# PCB-2x8GPIO-U.net
KiCad netlist of a schematic drawn in EAGLE
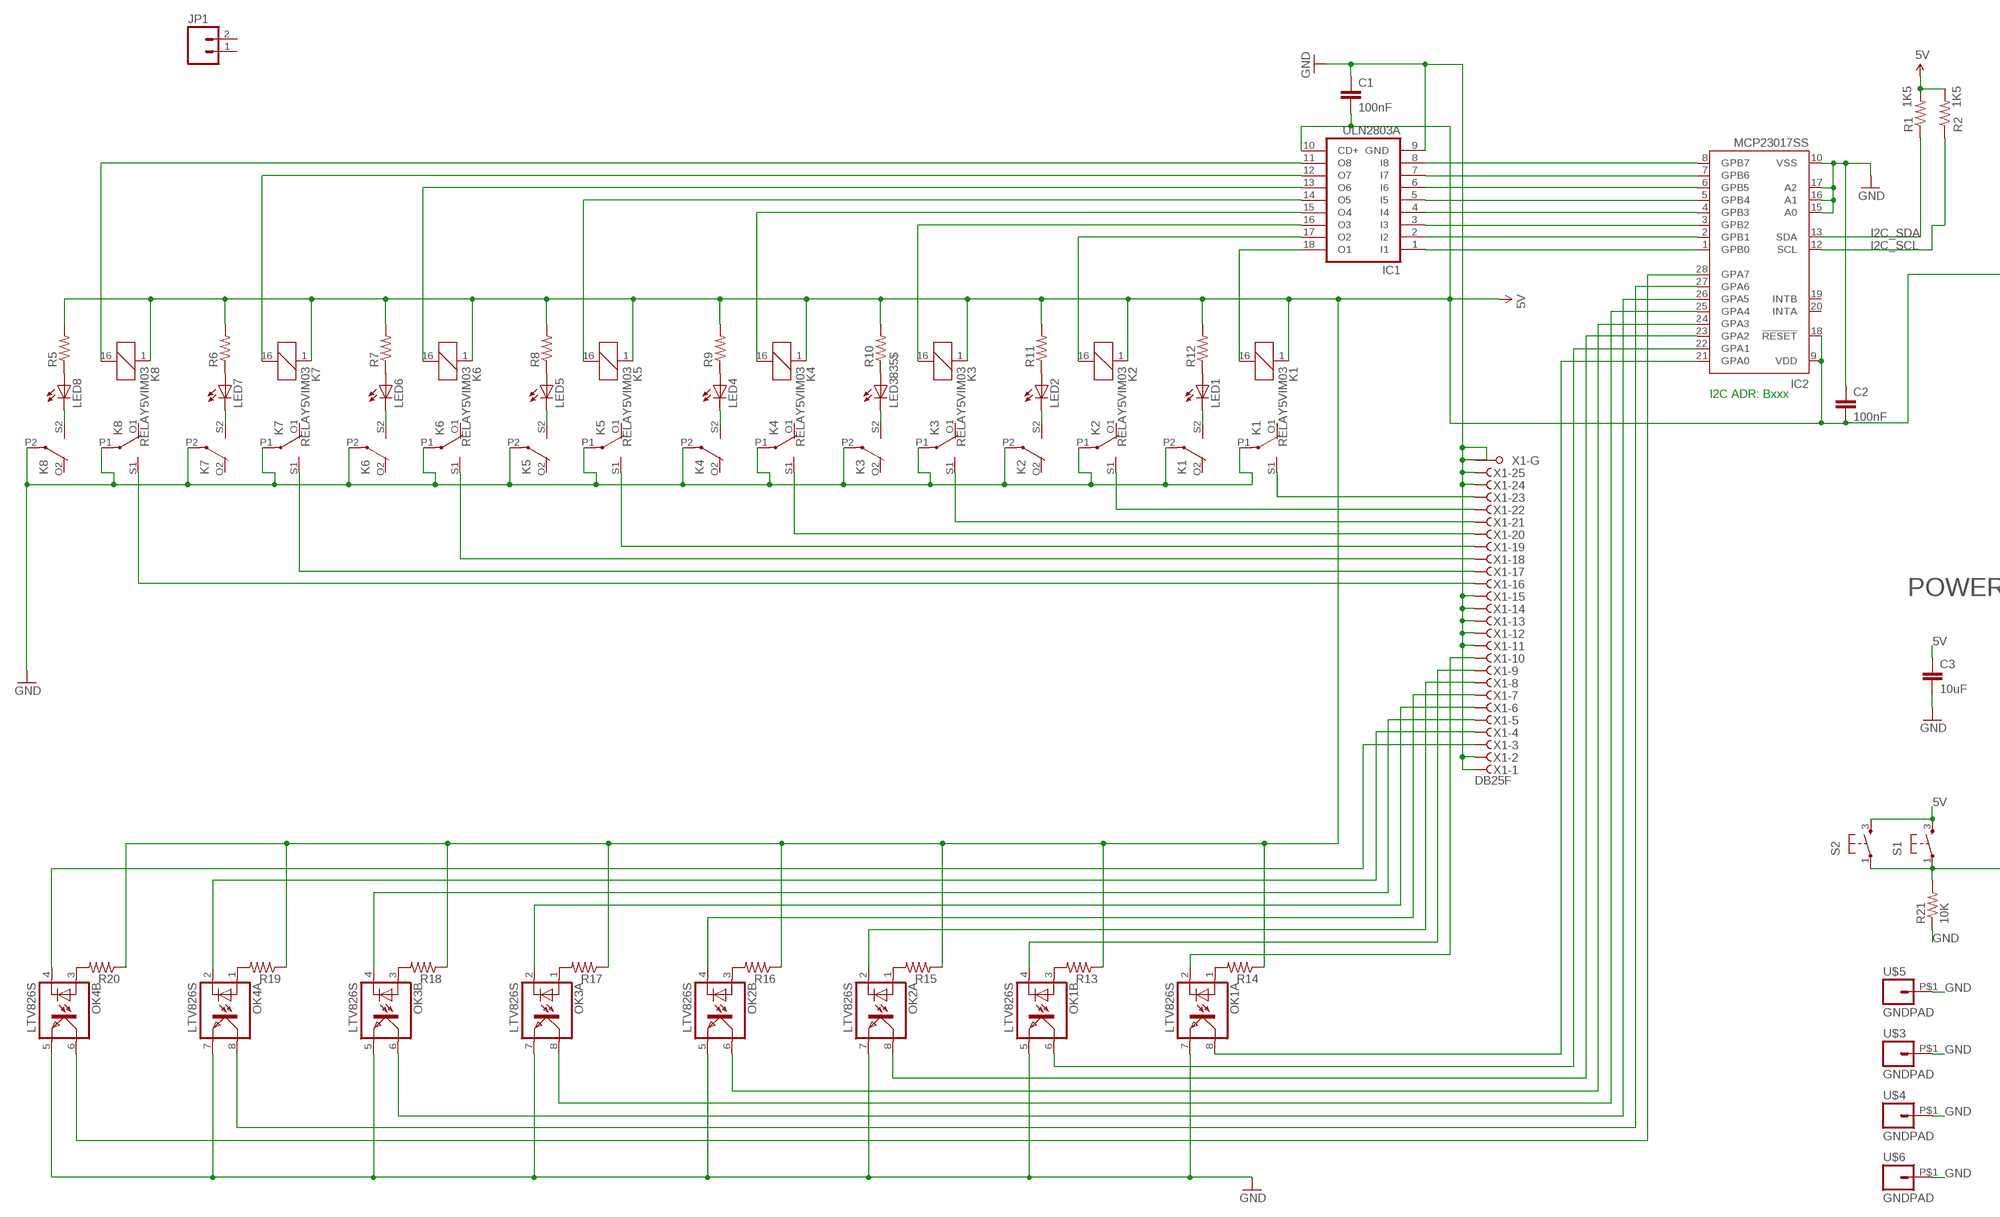
[diagram p0: schematic, sheet 1, part 1 of 2]
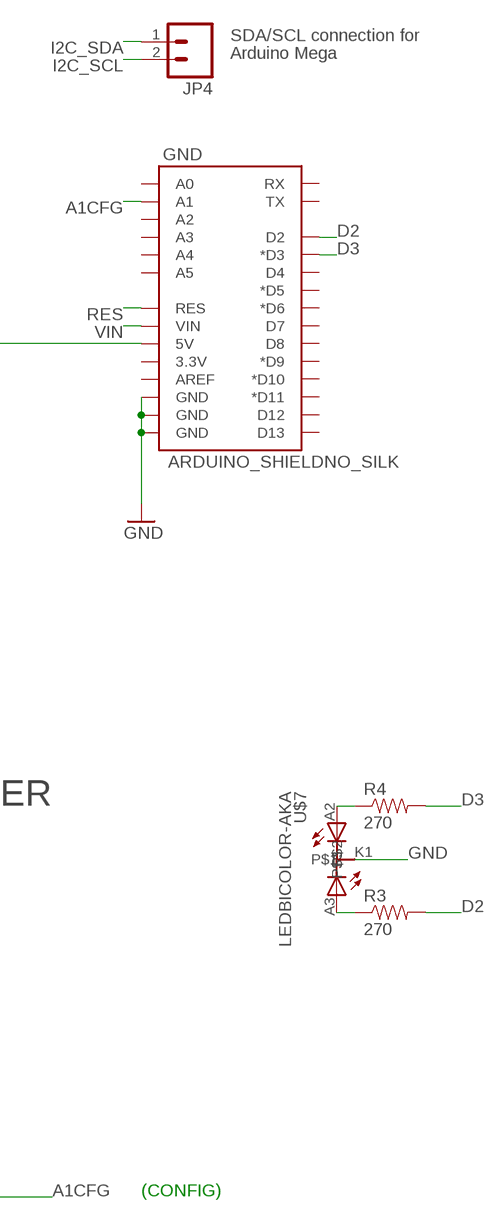
[diagram p1: schematic, sheet 1, part 2 of 2]

(export (version "E")
  (design (tool "Eeschema 10.0.6"))
  (components
    (comp (ref "C1")
      (value "100nF")
      (footprint "eagle-import:0805")
      (libsource (lib "eagle-import") (part "CAP0805"))
    )
    (comp (ref "C2")
      (value "100nF")
      (footprint "eagle-import:0603-CAP")
      (libsource (lib "eagle-import") (part "CAP0603-CAP"))
    )
    (comp (ref "C3")
      (value "10uF")
      (footprint "eagle-import:0805")
      (libsource (lib "eagle-import") (part "CAP0805"))
    )
    (comp (ref "GND")
      (value "ARDUINO_SHIELDNO_SILK")
      (footprint "eagle-import:DUEMILANOVE_VIAS")
      (libsource (lib "eagle-import") (part "ARDUINO_SHIELDNO_SILK"))
    )
    (comp (ref "IC1")
      (value "ULN2803A")
      (footprint "eagle-import:SO18W")
      (libsource (lib "eagle-import") (part "ULN2803ASO18W"))
    )
    (comp (ref "IC2")
      (value "MCP23017SS")
      (footprint "eagle-import:SSOP28")
      (fields (field (name "MF") "MICROCHIP") (field (name "MPN") "MCP23017-E/SS"))
      (libsource (lib "eagle-import") (part "MCP23017SS"))
    )
    (comp (ref "JP1")
      (value "M02PTH")
      (footprint "eagle-import:1X02")
      (libsource (lib "eagle-import") (part "M02PTH"))
    )
    (comp (ref "JP4")
      (value "M02PTH")
      (footprint "eagle-import:1X02")
      (libsource (lib "eagle-import") (part "M02PTH"))
    )
    (comp (ref "K1")
      (value "RELAY5VIM03")
      (footprint "eagle-import:DS2Y")
      (libsource (lib "eagle-import") (part "RELAY5VIM03"))
    )
    (comp (ref "K2")
      (value "RELAY5VIM03")
      (footprint "eagle-import:DS2Y")
      (libsource (lib "eagle-import") (part "RELAY5VIM03"))
    )
    (comp (ref "K3")
      (value "RELAY5VIM03")
      (footprint "eagle-import:DS2Y")
      (libsource (lib "eagle-import") (part "RELAY5VIM03"))
    )
    (comp (ref "K4")
      (value "RELAY5VIM03")
      (footprint "eagle-import:DS2Y")
      (libsource (lib "eagle-import") (part "RELAY5VIM03"))
    )
    (comp (ref "K5")
      (value "RELAY5VIM03")
      (footprint "eagle-import:DS2Y")
      (libsource (lib "eagle-import") (part "RELAY5VIM03"))
    )
    (comp (ref "K6")
      (value "RELAY5VIM03")
      (footprint "eagle-import:DS2Y")
      (libsource (lib "eagle-import") (part "RELAY5VIM03"))
    )
    (comp (ref "K7")
      (value "RELAY5VIM03")
      (footprint "eagle-import:DS2Y")
      (libsource (lib "eagle-import") (part "RELAY5VIM03"))
    )
    (comp (ref "K8")
      (value "RELAY5VIM03")
      (footprint "eagle-import:DS2Y")
      (libsource (lib "eagle-import") (part "RELAY5VIM03"))
    )
    (comp (ref "LED1")
      (value "LED1206")
      (footprint "eagle-import:LED-1206")
      (libsource (lib "eagle-import") (part "LED1206"))
    )
    (comp (ref "LED2")
      (value "LED1206")
      (footprint "eagle-import:LED-1206")
      (libsource (lib "eagle-import") (part "LED1206"))
    )
    (comp (ref "LED4")
      (value "LED1206")
      (footprint "eagle-import:LED-1206")
      (libsource (lib "eagle-import") (part "LED1206"))
    )
    (comp (ref "LED5")
      (value "LED1206")
      (footprint "eagle-import:LED-1206")
      (libsource (lib "eagle-import") (part "LED1206"))
    )
    (comp (ref "LED6")
      (value "LED1206")
      (footprint "eagle-import:LED-1206")
      (libsource (lib "eagle-import") (part "LED1206"))
    )
    (comp (ref "LED7")
      (value "LED1206")
      (footprint "eagle-import:LED-1206")
      (libsource (lib "eagle-import") (part "LED1206"))
    )
    (comp (ref "LED8")
      (value "LED1206")
      (footprint "eagle-import:LED-1206")
      (libsource (lib "eagle-import") (part "LED1206"))
    )
    (comp (ref "LED3835$")
      (value "LED1206")
      (footprint "eagle-import:LED-1206")
      (libsource (lib "eagle-import") (part "LED1206"))
    )
    (comp (ref "OK1")
      (value "LTV826S")
      (footprint "eagle-import:DIL8-SMD")
      (libsource (lib "eagle-import") (part "LTV826S"))
    )
    (comp (ref "OK2")
      (value "LTV826S")
      (footprint "eagle-import:DIL8-SMD")
      (libsource (lib "eagle-import") (part "LTV826S"))
    )
    (comp (ref "OK3")
      (value "LTV826S")
      (footprint "eagle-import:DIL8-SMD")
      (libsource (lib "eagle-import") (part "LTV826S"))
    )
    (comp (ref "OK4")
      (value "LTV826S")
      (footprint "eagle-import:DIL8-SMD")
      (libsource (lib "eagle-import") (part "LTV826S"))
    )
    (comp (ref "R1")
      (value "1K5")
      (footprint "eagle-import:0603-RES")
      (libsource (lib "eagle-import") (part "RESISTOR0603-RES"))
    )
    (comp (ref "R2")
      (value "1K5")
      (footprint "eagle-import:0603-RES")
      (libsource (lib "eagle-import") (part "RESISTOR0603-RES"))
    )
    (comp (ref "R3")
      (value "270")
      (footprint "eagle-import:0603-RES")
      (libsource (lib "eagle-import") (part "RESISTOR0603-RES"))
    )
    (comp (ref "R4")
      (value "270")
      (footprint "eagle-import:0603-RES")
      (libsource (lib "eagle-import") (part "RESISTOR0603-RES"))
    )
    (comp (ref "R5")
      (value "RESISTOR0603-RES")
      (footprint "eagle-import:0603-RES")
      (libsource (lib "eagle-import") (part "RESISTOR0603-RES"))
    )
    (comp (ref "R6")
      (value "RESISTOR0603-RES")
      (footprint "eagle-import:0603-RES")
      (libsource (lib "eagle-import") (part "RESISTOR0603-RES"))
    )
    (comp (ref "R7")
      (value "RESISTOR0603-RES")
      (footprint "eagle-import:0603-RES")
      (libsource (lib "eagle-import") (part "RESISTOR0603-RES"))
    )
    (comp (ref "R8")
      (value "RESISTOR0603-RES")
      (footprint "eagle-import:0603-RES")
      (libsource (lib "eagle-import") (part "RESISTOR0603-RES"))
    )
    (comp (ref "R9")
      (value "RESISTOR0603-RES")
      (footprint "eagle-import:0603-RES")
      (libsource (lib "eagle-import") (part "RESISTOR0603-RES"))
    )
    (comp (ref "R10")
      (value "RESISTOR0603-RES")
      (footprint "eagle-import:0603-RES")
      (libsource (lib "eagle-import") (part "RESISTOR0603-RES"))
    )
    (comp (ref "R11")
      (value "RESISTOR0603-RES")
      (footprint "eagle-import:0603-RES")
      (libsource (lib "eagle-import") (part "RESISTOR0603-RES"))
    )
    (comp (ref "R12")
      (value "RESISTOR0603-RES")
      (footprint "eagle-import:0603-RES")
      (libsource (lib "eagle-import") (part "RESISTOR0603-RES"))
    )
    (comp (ref "R13")
      (value "RESISTOR0603-RES")
      (footprint "eagle-import:0603-RES")
      (libsource (lib "eagle-import") (part "RESISTOR0603-RES"))
    )
    (comp (ref "R14")
      (value "RESISTOR0603-RES")
      (footprint "eagle-import:0603-RES")
      (libsource (lib "eagle-import") (part "RESISTOR0603-RES"))
    )
    (comp (ref "R15")
      (value "RESISTOR0603-RES")
      (footprint "eagle-import:0603-RES")
      (libsource (lib "eagle-import") (part "RESISTOR0603-RES"))
    )
    (comp (ref "R16")
      (value "RESISTOR0603-RES")
      (footprint "eagle-import:0603-RES")
      (libsource (lib "eagle-import") (part "RESISTOR0603-RES"))
    )
    (comp (ref "R17")
      (value "RESISTOR0603-RES")
      (footprint "eagle-import:0603-RES")
      (libsource (lib "eagle-import") (part "RESISTOR0603-RES"))
    )
    (comp (ref "R18")
      (value "RESISTOR0603-RES")
      (footprint "eagle-import:0603-RES")
      (libsource (lib "eagle-import") (part "RESISTOR0603-RES"))
    )
    (comp (ref "R19")
      (value "RESISTOR0603-RES")
      (footprint "eagle-import:0603-RES")
      (libsource (lib "eagle-import") (part "RESISTOR0603-RES"))
    )
    (comp (ref "R20")
      (value "RESISTOR0603-RES")
      (footprint "eagle-import:0603-RES")
      (libsource (lib "eagle-import") (part "RESISTOR0603-RES"))
    )
    (comp (ref "R21")
      (value "10K")
      (footprint "eagle-import:0603-RES")
      (libsource (lib "eagle-import") (part "RESISTOR0603-RES"))
    )
    (comp (ref "S1")
      (value "TAC_SWITCH")
      (footprint "eagle-import:PUSHBUTTON")
      (libsource (lib "eagle-import") (part "TAC_SWITCH"))
    )
    (comp (ref "S2")
      (value "TAC_SWITCH")
      (footprint "eagle-import:PUSHBUTTON")
      (libsource (lib "eagle-import") (part "TAC_SWITCH"))
    )
    (comp (ref "U$3")
      (value "GNDPAD")
      (footprint "eagle-import:3.2MMPAD")
      (libsource (lib "eagle-import") (part "GNDPAD"))
    )
    (comp (ref "U$4")
      (value "GNDPAD")
      (footprint "eagle-import:3.2MMPAD")
      (libsource (lib "eagle-import") (part "GNDPAD"))
    )
    (comp (ref "U$5")
      (value "GNDPAD")
      (footprint "eagle-import:3.2MMPAD")
      (libsource (lib "eagle-import") (part "GNDPAD"))
    )
    (comp (ref "U$6")
      (value "GNDPAD")
      (footprint "eagle-import:3.2MMPAD")
      (libsource (lib "eagle-import") (part "GNDPAD"))
    )
    (comp (ref "U$7")
      (value "LEDBICOLOR-AKA")
      (footprint "eagle-import:LED5MM-BICOLOR")
      (libsource (lib "eagle-import") (part "LEDBICOLOR-AKA"))
    )
    (comp (ref "X1")
      (value "DB25F")
      (footprint "eagle-import:F25HP")
      (libsource (lib "eagle-import") (part "F25HPS"))
    )
  )
  (nets
    (net (code "1") (name "5V") (class "Default")
      (node (ref "C1") (pin "2") (pinfunction "2_2") (pintype "passive"))
      (node (ref "C2") (pin "2") (pinfunction "2_2") (pintype "passive"))
      (node (ref "C3") (pin "1") (pinfunction "1_1") (pintype "passive"))
      (node (ref "GND") (pin "5V") (pinfunction "5V_5V") (pintype "bidirectional"))
      (node (ref "IC1") (pin "10") (pinfunction "CD+_10") (pintype "passive"))
      (node (ref "IC2") (pin "18") (pinfunction "~{RESET}_18") (pintype "input"))
      (node (ref "IC2") (pin "9") (pinfunction "VDD_9") (pintype "power_in"))
      (node (ref "K1") (pin "1") (pinfunction "1_1") (pintype "passive"))
      (node (ref "K2") (pin "1") (pinfunction "1_1") (pintype "passive"))
      (node (ref "K3") (pin "1") (pinfunction "1_1") (pintype "passive"))
      (node (ref "K4") (pin "1") (pinfunction "1_1") (pintype "passive"))
      (node (ref "K5") (pin "1") (pinfunction "1_1") (pintype "passive"))
      (node (ref "K6") (pin "1") (pinfunction "1_1") (pintype "passive"))
      (node (ref "K7") (pin "1") (pinfunction "1_1") (pintype "passive"))
      (node (ref "K8") (pin "1") (pinfunction "1_1") (pintype "passive"))
      (node (ref "R1") (pin "2") (pinfunction "2_2") (pintype "passive"))
      (node (ref "R10") (pin "2") (pinfunction "2_2") (pintype "passive"))
      (node (ref "R11") (pin "2") (pinfunction "2_2") (pintype "passive"))
      (node (ref "R12") (pin "2") (pinfunction "2_2") (pintype "passive"))
      (node (ref "R13") (pin "1") (pinfunction "1_1") (pintype "passive"))
      (node (ref "R14") (pin "1") (pinfunction "1_1") (pintype "passive"))
      (node (ref "R15") (pin "1") (pinfunction "1_1") (pintype "passive"))
      (node (ref "R16") (pin "1") (pinfunction "1_1") (pintype "passive"))
      (node (ref "R17") (pin "1") (pinfunction "1_1") (pintype "passive"))
      (node (ref "R18") (pin "1") (pinfunction "1_1") (pintype "passive"))
      (node (ref "R19") (pin "1") (pinfunction "1_1") (pintype "passive"))
      (node (ref "R2") (pin "2") (pinfunction "2_2") (pintype "passive"))
      (node (ref "R20") (pin "1") (pinfunction "1_1") (pintype "passive"))
      (node (ref "R5") (pin "2") (pinfunction "2_2") (pintype "passive"))
      (node (ref "R6") (pin "2") (pinfunction "2_2") (pintype "passive"))
      (node (ref "R7") (pin "2") (pinfunction "2_2") (pintype "passive"))
      (node (ref "R8") (pin "2") (pinfunction "2_2") (pintype "passive"))
      (node (ref "R9") (pin "2") (pinfunction "2_2") (pintype "passive"))
      (node (ref "S1") (pin "3") (pinfunction "3_3") (pintype "passive"))
      (node (ref "S2") (pin "3") (pinfunction "3_3") (pintype "passive"))
    )
    (net (code "2") (name "A1CFG") (class "Default")
      (node (ref "GND") (pin "A1") (pinfunction "A1_A1") (pintype "bidirectional"))
      (node (ref "R21") (pin "2") (pinfunction "2_2") (pintype "passive"))
      (node (ref "S1") (pin "1") (pinfunction "1_1") (pintype "passive"))
      (node (ref "S2") (pin "1") (pinfunction "1_1") (pintype "passive"))
    )
    (net (code "3") (name "D2") (class "Default")
      (node (ref "GND") (pin "D2") (pinfunction "D2_D2") (pintype "bidirectional"))
      (node (ref "R3") (pin "2") (pinfunction "2_2") (pintype "passive"))
    )
    (net (code "4") (name "D3") (class "Default")
      (node (ref "GND") (pin "D3") (pinfunction "*D3_D3") (pintype "bidirectional"))
      (node (ref "R4") (pin "2") (pinfunction "2_2") (pintype "passive"))
    )
    (net (code "5") (name "GND") (class "Default")
      (node (ref "C1") (pin "1") (pinfunction "1_1") (pintype "passive"))
      (node (ref "C2") (pin "1") (pinfunction "1_1") (pintype "passive"))
      (node (ref "C3") (pin "2") (pinfunction "2_2") (pintype "passive"))
      (node (ref "GND") (pin "GND@0") (pinfunction "GND_GND@0") (pintype "bidirectional"))
      (node (ref "GND") (pin "GND@1") (pinfunction "GND_GND@1") (pintype "bidirectional"))
      (node (ref "GND") (pin "GND@2") (pinfunction "GND_GND@2") (pintype "bidirectional"))
      (node (ref "IC1") (pin "9") (pinfunction "GND_9") (pintype "power_in"))
      (node (ref "IC2") (pin "10") (pinfunction "VSS_10") (pintype "power_in"))
      (node (ref "IC2") (pin "15") (pinfunction "A0_15") (pintype "input"))
      (node (ref "IC2") (pin "16") (pinfunction "A1_16") (pintype "input"))
      (node (ref "IC2") (pin "17") (pinfunction "A2_17") (pintype "input"))
      (node (ref "K1") (pin "P1") (pinfunction "P_P1") (pintype "passive"))
      (node (ref "K1") (pin "P2") (pinfunction "P_P2") (pintype "passive"))
      (node (ref "K2") (pin "P1") (pinfunction "P_P1") (pintype "passive"))
      (node (ref "K2") (pin "P2") (pinfunction "P_P2") (pintype "passive"))
      (node (ref "K3") (pin "P1") (pinfunction "P_P1") (pintype "passive"))
      (node (ref "K3") (pin "P2") (pinfunction "P_P2") (pintype "passive"))
      (node (ref "K4") (pin "P1") (pinfunction "P_P1") (pintype "passive"))
      (node (ref "K4") (pin "P2") (pinfunction "P_P2") (pintype "passive"))
      (node (ref "K5") (pin "P1") (pinfunction "P_P1") (pintype "passive"))
      (node (ref "K5") (pin "P2") (pinfunction "P_P2") (pintype "passive"))
      (node (ref "K6") (pin "P1") (pinfunction "P_P1") (pintype "passive"))
      (node (ref "K6") (pin "P2") (pinfunction "P_P2") (pintype "passive"))
      (node (ref "K7") (pin "P1") (pinfunction "P_P1") (pintype "passive"))
      (node (ref "K7") (pin "P2") (pinfunction "P_P2") (pintype "passive"))
      (node (ref "K8") (pin "P1") (pinfunction "P_P1") (pintype "passive"))
      (node (ref "K8") (pin "P2") (pinfunction "P_P2") (pintype "passive"))
      (node (ref "OK1") (pin "5") (pinfunction "EMIT_5") (pintype "passive"))
      (node (ref "OK1") (pin "7") (pinfunction "EMIT_7") (pintype "passive"))
      (node (ref "OK2") (pin "5") (pinfunction "EMIT_5") (pintype "passive"))
      (node (ref "OK2") (pin "7") (pinfunction "EMIT_7") (pintype "passive"))
      (node (ref "OK3") (pin "5") (pinfunction "EMIT_5") (pintype "passive"))
      (node (ref "OK3") (pin "7") (pinfunction "EMIT_7") (pintype "passive"))
      (node (ref "OK4") (pin "5") (pinfunction "EMIT_5") (pintype "passive"))
      (node (ref "OK4") (pin "7") (pinfunction "EMIT_7") (pintype "passive"))
      (node (ref "R21") (pin "1") (pinfunction "1_1") (pintype "passive"))
      (node (ref "U$3") (pin "P$1") (pinfunction "1_P$1") (pintype "passive"))
      (node (ref "U$4") (pin "P$1") (pinfunction "1_P$1") (pintype "passive"))
      (node (ref "U$5") (pin "P$1") (pinfunction "1_P$1") (pintype "passive"))
      (node (ref "U$6") (pin "P$1") (pinfunction "1_P$1") (pintype "passive"))
      (node (ref "U$7") (pin "K1") (pinfunction "P$1_K1") (pintype "bidirectional"))
      (node (ref "X1") (pin "1") (pinfunction "F_1") (pintype "passive"))
      (node (ref "X1") (pin "11") (pinfunction "F_11") (pintype "passive"))
      (node (ref "X1") (pin "12") (pinfunction "F_12") (pintype "passive"))
      (node (ref "X1") (pin "13") (pinfunction "F_13") (pintype "passive"))
      (node (ref "X1") (pin "14") (pinfunction "F_14") (pintype "passive"))
      (node (ref "X1") (pin "15") (pinfunction "F_15") (pintype "passive"))
      (node (ref "X1") (pin "2") (pinfunction "F_2") (pintype "passive"))
      (node (ref "X1") (pin "24") (pinfunction "F_24") (pintype "passive"))
      (node (ref "X1") (pin "25") (pinfunction "F_25") (pintype "passive"))
      (node (ref "X1") (pin "G1") (pinfunction "G1_G1") (pintype "passive"))
      (node (ref "X1") (pin "G2") (pinfunction "G2_G2") (pintype "passive"))
    )
    (net (code "6") (name "I2C_SCL") (class "Default")
      (node (ref "IC2") (pin "12") (pinfunction "SCL_12") (pintype "input"))
      (node (ref "JP4") (pin "2") (pinfunction "2_2") (pintype "passive"))
      (node (ref "R2") (pin "1") (pinfunction "1_1") (pintype "passive"))
    )
    (net (code "7") (name "I2C_SDA") (class "Default")
      (node (ref "IC2") (pin "13") (pinfunction "SDA_13") (pintype "bidirectional"))
      (node (ref "JP4") (pin "1") (pinfunction "1_1") (pintype "passive"))
      (node (ref "R1") (pin "1") (pinfunction "1_1") (pintype "passive"))
    )
    (net (code "8") (name "Net-(IC1-I1)") (class "Default")
      (node (ref "IC1") (pin "1") (pinfunction "I1_1") (pintype "input"))
      (node (ref "IC2") (pin "1") (pinfunction "GPB0_1") (pintype "bidirectional"))
    )
    (net (code "9") (name "Net-(IC1-I2)") (class "Default")
      (node (ref "IC1") (pin "2") (pinfunction "I2_2") (pintype "input"))
      (node (ref "IC2") (pin "2") (pinfunction "GPB1_2") (pintype "bidirectional"))
    )
    (net (code "10") (name "Net-(IC1-I3)") (class "Default")
      (node (ref "IC1") (pin "3") (pinfunction "I3_3") (pintype "input"))
      (node (ref "IC2") (pin "3") (pinfunction "GPB2_3") (pintype "bidirectional"))
    )
    (net (code "11") (name "Net-(IC1-I4)") (class "Default")
      (node (ref "IC1") (pin "4") (pinfunction "I4_4") (pintype "input"))
      (node (ref "IC2") (pin "4") (pinfunction "GPB3_4") (pintype "bidirectional"))
    )
    (net (code "12") (name "Net-(IC1-I5)") (class "Default")
      (node (ref "IC1") (pin "5") (pinfunction "I5_5") (pintype "input"))
      (node (ref "IC2") (pin "5") (pinfunction "GPB4_5") (pintype "bidirectional"))
    )
    (net (code "13") (name "Net-(IC1-I6)") (class "Default")
      (node (ref "IC1") (pin "6") (pinfunction "I6_6") (pintype "input"))
      (node (ref "IC2") (pin "6") (pinfunction "GPB5_6") (pintype "bidirectional"))
    )
    (net (code "14") (name "Net-(IC1-I7)") (class "Default")
      (node (ref "IC1") (pin "7") (pinfunction "I7_7") (pintype "input"))
      (node (ref "IC2") (pin "7") (pinfunction "GPB6_7") (pintype "bidirectional"))
    )
    (net (code "15") (name "Net-(IC1-I8)") (class "Default")
      (node (ref "IC1") (pin "8") (pinfunction "I8_8") (pintype "input"))
      (node (ref "IC2") (pin "8") (pinfunction "GPB7_8") (pintype "bidirectional"))
    )
    (net (code "16") (name "Net-(IC1-O1)") (class "Default")
      (node (ref "IC1") (pin "18") (pinfunction "O1_18") (pintype "open_collector"))
      (node (ref "K1") (pin "16") (pinfunction "2_16") (pintype "passive"))
    )
    (net (code "17") (name "Net-(IC1-O2)") (class "Default")
      (node (ref "IC1") (pin "17") (pinfunction "O2_17") (pintype "open_collector"))
      (node (ref "K2") (pin "16") (pinfunction "2_16") (pintype "passive"))
    )
    (net (code "18") (name "Net-(IC1-O3)") (class "Default")
      (node (ref "IC1") (pin "16") (pinfunction "O3_16") (pintype "open_collector"))
      (node (ref "K3") (pin "16") (pinfunction "2_16") (pintype "passive"))
    )
    (net (code "19") (name "Net-(IC1-O4)") (class "Default")
      (node (ref "IC1") (pin "15") (pinfunction "O4_15") (pintype "open_collector"))
      (node (ref "K4") (pin "16") (pinfunction "2_16") (pintype "passive"))
    )
    (net (code "20") (name "Net-(IC1-O5)") (class "Default")
      (node (ref "IC1") (pin "14") (pinfunction "O5_14") (pintype "open_collector"))
      (node (ref "K5") (pin "16") (pinfunction "2_16") (pintype "passive"))
    )
    (net (code "21") (name "Net-(IC1-O6)") (class "Default")
      (node (ref "IC1") (pin "13") (pinfunction "O6_13") (pintype "open_collector"))
      (node (ref "K6") (pin "16") (pinfunction "2_16") (pintype "passive"))
    )
    (net (code "22") (name "Net-(IC1-O7)") (class "Default")
      (node (ref "IC1") (pin "12") (pinfunction "O7_12") (pintype "open_collector"))
      (node (ref "K7") (pin "16") (pinfunction "2_16") (pintype "passive"))
    )
    (net (code "23") (name "Net-(IC1-O8)") (class "Default")
      (node (ref "IC1") (pin "11") (pinfunction "O8_11") (pintype "open_collector"))
      (node (ref "K8") (pin "16") (pinfunction "2_16") (pintype "passive"))
    )
    (net (code "24") (name "Net-(IC2-GPA0)") (class "Default")
      (node (ref "IC2") (pin "21") (pinfunction "GPA0_21") (pintype "bidirectional"))
      (node (ref "OK1") (pin "8") (pinfunction "COL_8") (pintype "passive"))
    )
    (net (code "25") (name "Net-(IC2-GPA1)") (class "Default")
      (node (ref "IC2") (pin "22") (pinfunction "GPA1_22") (pintype "bidirectional"))
      (node (ref "OK1") (pin "6") (pinfunction "COL_6") (pintype "passive"))
    )
    (net (code "26") (name "Net-(IC2-GPA2)") (class "Default")
      (node (ref "IC2") (pin "23") (pinfunction "GPA2_23") (pintype "bidirectional"))
      (node (ref "OK2") (pin "8") (pinfunction "COL_8") (pintype "passive"))
    )
    (net (code "27") (name "Net-(IC2-GPA3)") (class "Default")
      (node (ref "IC2") (pin "24") (pinfunction "GPA3_24") (pintype "bidirectional"))
      (node (ref "OK2") (pin "6") (pinfunction "COL_6") (pintype "passive"))
    )
    (net (code "28") (name "Net-(IC2-GPA4)") (class "Default")
      (node (ref "IC2") (pin "25") (pinfunction "GPA4_25") (pintype "bidirectional"))
      (node (ref "OK3") (pin "8") (pinfunction "COL_8") (pintype "passive"))
    )
    (net (code "29") (name "Net-(IC2-GPA5)") (class "Default")
      (node (ref "IC2") (pin "26") (pinfunction "GPA5_26") (pintype "bidirectional"))
      (node (ref "OK3") (pin "6") (pinfunction "COL_6") (pintype "passive"))
    )
    (net (code "30") (name "Net-(IC2-GPA6)") (class "Default")
      (node (ref "IC2") (pin "27") (pinfunction "GPA6_27") (pintype "bidirectional"))
      (node (ref "OK4") (pin "8") (pinfunction "COL_8") (pintype "passive"))
    )
    (net (code "31") (name "Net-(IC2-GPA7)") (class "Default")
      (node (ref "IC2") (pin "28") (pinfunction "GPA7_28") (pintype "bidirectional"))
      (node (ref "OK4") (pin "6") (pinfunction "COL_6") (pintype "passive"))
    )
    (net (code "32") (name "Net-(K1B-S)") (class "Default")
      (node (ref "K1") (pin "S1") (pinfunction "S_S1") (pintype "passive"))
      (node (ref "X1") (pin "23") (pinfunction "F_23") (pintype "passive"))
    )
    (net (code "33") (name "Net-(K1C-S)") (class "Default")
      (node (ref "K1") (pin "S2") (pinfunction "S_S2") (pintype "passive"))
      (node (ref "LED1") (pin "C") (pinfunction "C_C") (pintype "passive"))
    )
    (net (code "34") (name "Net-(K2B-S)") (class "Default")
      (node (ref "K2") (pin "S1") (pinfunction "S_S1") (pintype "passive"))
      (node (ref "X1") (pin "22") (pinfunction "F_22") (pintype "passive"))
    )
    (net (code "35") (name "Net-(K2C-S)") (class "Default")
      (node (ref "K2") (pin "S2") (pinfunction "S_S2") (pintype "passive"))
      (node (ref "LED2") (pin "C") (pinfunction "C_C") (pintype "passive"))
    )
    (net (code "36") (name "Net-(K3B-S)") (class "Default")
      (node (ref "K3") (pin "S1") (pinfunction "S_S1") (pintype "passive"))
      (node (ref "X1") (pin "21") (pinfunction "F_21") (pintype "passive"))
    )
    (net (code "37") (name "Net-(K3C-S)") (class "Default")
      (node (ref "K3") (pin "S2") (pinfunction "S_S2") (pintype "passive"))
      (node (ref "LED3835$") (pin "C") (pinfunction "C_C") (pintype "passive"))
    )
    (net (code "38") (name "Net-(K4B-S)") (class "Default")
      (node (ref "K4") (pin "S1") (pinfunction "S_S1") (pintype "passive"))
      (node (ref "X1") (pin "20") (pinfunction "F_20") (pintype "passive"))
    )
    (net (code "39") (name "Net-(K4C-S)") (class "Default")
      (node (ref "K4") (pin "S2") (pinfunction "S_S2") (pintype "passive"))
      (node (ref "LED4") (pin "C") (pinfunction "C_C") (pintype "passive"))
    )
    (net (code "40") (name "Net-(K5B-S)") (class "Default")
      (node (ref "K5") (pin "S1") (pinfunction "S_S1") (pintype "passive"))
      (node (ref "X1") (pin "19") (pinfunction "F_19") (pintype "passive"))
    )
    (net (code "41") (name "Net-(K5C-S)") (class "Default")
      (node (ref "K5") (pin "S2") (pinfunction "S_S2") (pintype "passive"))
      (node (ref "LED5") (pin "C") (pinfunction "C_C") (pintype "passive"))
    )
    (net (code "42") (name "Net-(K6B-S)") (class "Default")
      (node (ref "K6") (pin "S1") (pinfunction "S_S1") (pintype "passive"))
      (node (ref "X1") (pin "18") (pinfunction "F_18") (pintype "passive"))
    )
    (net (code "43") (name "Net-(K6C-S)") (class "Default")
      (node (ref "K6") (pin "S2") (pinfunction "S_S2") (pintype "passive"))
      (node (ref "LED6") (pin "C") (pinfunction "C_C") (pintype "passive"))
    )
    (net (code "44") (name "Net-(K7B-S)") (class "Default")
      (node (ref "K7") (pin "S1") (pinfunction "S_S1") (pintype "passive"))
      (node (ref "X1") (pin "17") (pinfunction "F_17") (pintype "passive"))
    )
    (net (code "45") (name "Net-(K7C-S)") (class "Default")
      (node (ref "K7") (pin "S2") (pinfunction "S_S2") (pintype "passive"))
      (node (ref "LED7") (pin "C") (pinfunction "C_C") (pintype "passive"))
    )
    (net (code "46") (name "Net-(K8B-S)") (class "Default")
      (node (ref "K8") (pin "S1") (pinfunction "S_S1") (pintype "passive"))
      (node (ref "X1") (pin "16") (pinfunction "F_16") (pintype "passive"))
    )
    (net (code "47") (name "Net-(K8C-S)") (class "Default")
      (node (ref "K8") (pin "S2") (pinfunction "S_S2") (pintype "passive"))
      (node (ref "LED8") (pin "C") (pinfunction "C_C") (pintype "passive"))
    )
    (net (code "48") (name "Net-(LED1-PadA)") (class "Default")
      (node (ref "LED1") (pin "A") (pinfunction "A_A") (pintype "passive"))
      (node (ref "R12") (pin "1") (pinfunction "1_1") (pintype "passive"))
    )
    (net (code "49") (name "Net-(LED2-PadA)") (class "Default")
      (node (ref "LED2") (pin "A") (pinfunction "A_A") (pintype "passive"))
      (node (ref "R11") (pin "1") (pinfunction "1_1") (pintype "passive"))
    )
    (net (code "50") (name "Net-(LED4-PadA)") (class "Default")
      (node (ref "LED4") (pin "A") (pinfunction "A_A") (pintype "passive"))
      (node (ref "R9") (pin "1") (pinfunction "1_1") (pintype "passive"))
    )
    (net (code "51") (name "Net-(LED5-PadA)") (class "Default")
      (node (ref "LED5") (pin "A") (pinfunction "A_A") (pintype "passive"))
      (node (ref "R8") (pin "1") (pinfunction "1_1") (pintype "passive"))
    )
    (net (code "52") (name "Net-(LED6-PadA)") (class "Default")
      (node (ref "LED6") (pin "A") (pinfunction "A_A") (pintype "passive"))
      (node (ref "R7") (pin "1") (pinfunction "1_1") (pintype "passive"))
    )
    (net (code "53") (name "Net-(LED7-PadA)") (class "Default")
      (node (ref "LED7") (pin "A") (pinfunction "A_A") (pintype "passive"))
      (node (ref "R6") (pin "1") (pinfunction "1_1") (pintype "passive"))
    )
    (net (code "54") (name "Net-(LED8-PadA)") (class "Default")
      (node (ref "LED8") (pin "A") (pinfunction "A_A") (pintype "passive"))
      (node (ref "R5") (pin "1") (pinfunction "1_1") (pintype "passive"))
    )
    (net (code "55") (name "Net-(LED3835$-PadA)") (class "Default")
      (node (ref "LED3835$") (pin "A") (pinfunction "A_A") (pintype "passive"))
      (node (ref "R10") (pin "1") (pinfunction "1_1") (pintype "passive"))
    )
    (net (code "56") (name "Net-(OK1A-A)") (class "Default")
      (node (ref "OK1") (pin "1") (pinfunction "A_1") (pintype "passive"))
      (node (ref "R14") (pin "2") (pinfunction "2_2") (pintype "passive"))
    )
    (net (code "57") (name "Net-(OK1A-C)") (class "Default")
      (node (ref "OK1") (pin "2") (pinfunction "C_2") (pintype "passive"))
      (node (ref "X1") (pin "10") (pinfunction "F_10") (pintype "passive"))
    )
    (net (code "58") (name "Net-(OK1B-A)") (class "Default")
      (node (ref "OK1") (pin "3") (pinfunction "A_3") (pintype "passive"))
      (node (ref "R13") (pin "2") (pinfunction "2_2") (pintype "passive"))
    )
    (net (code "59") (name "Net-(OK1B-C)") (class "Default")
      (node (ref "OK1") (pin "4") (pinfunction "C_4") (pintype "passive"))
      (node (ref "X1") (pin "9") (pinfunction "F_9") (pintype "passive"))
    )
    (net (code "60") (name "Net-(OK2A-A)") (class "Default")
      (node (ref "OK2") (pin "1") (pinfunction "A_1") (pintype "passive"))
      (node (ref "R15") (pin "2") (pinfunction "2_2") (pintype "passive"))
    )
    (net (code "61") (name "Net-(OK2A-C)") (class "Default")
      (node (ref "OK2") (pin "2") (pinfunction "C_2") (pintype "passive"))
      (node (ref "X1") (pin "8") (pinfunction "F_8") (pintype "passive"))
    )
    (net (code "62") (name "Net-(OK2B-A)") (class "Default")
      (node (ref "OK2") (pin "3") (pinfunction "A_3") (pintype "passive"))
      (node (ref "R16") (pin "2") (pinfunction "2_2") (pintype "passive"))
    )
    (net (code "63") (name "Net-(OK2B-C)") (class "Default")
      (node (ref "OK2") (pin "4") (pinfunction "C_4") (pintype "passive"))
      (node (ref "X1") (pin "7") (pinfunction "F_7") (pintype "passive"))
    )
    (net (code "64") (name "Net-(OK3A-A)") (class "Default")
      (node (ref "OK3") (pin "1") (pinfunction "A_1") (pintype "passive"))
      (node (ref "R17") (pin "2") (pinfunction "2_2") (pintype "passive"))
    )
    (net (code "65") (name "Net-(OK3A-C)") (class "Default")
      (node (ref "OK3") (pin "2") (pinfunction "C_2") (pintype "passive"))
      (node (ref "X1") (pin "6") (pinfunction "F_6") (pintype "passive"))
    )
    (net (code "66") (name "Net-(OK3B-A)") (class "Default")
      (node (ref "OK3") (pin "3") (pinfunction "A_3") (pintype "passive"))
      (node (ref "R18") (pin "2") (pinfunction "2_2") (pintype "passive"))
    )
    (net (code "67") (name "Net-(OK3B-C)") (class "Default")
      (node (ref "OK3") (pin "4") (pinfunction "C_4") (pintype "passive"))
      (node (ref "X1") (pin "5") (pinfunction "F_5") (pintype "passive"))
    )
    (net (code "68") (name "Net-(OK4A-A)") (class "Default")
      (node (ref "OK4") (pin "1") (pinfunction "A_1") (pintype "passive"))
      (node (ref "R19") (pin "2") (pinfunction "2_2") (pintype "passive"))
    )
    (net (code "69") (name "Net-(OK4A-C)") (class "Default")
      (node (ref "OK4") (pin "2") (pinfunction "C_2") (pintype "passive"))
      (node (ref "X1") (pin "4") (pinfunction "F_4") (pintype "passive"))
    )
    (net (code "70") (name "Net-(OK4B-A)") (class "Default")
      (node (ref "OK4") (pin "3") (pinfunction "A_3") (pintype "passive"))
      (node (ref "R20") (pin "2") (pinfunction "2_2") (pintype "passive"))
    )
    (net (code "71") (name "Net-(OK4B-C)") (class "Default")
      (node (ref "OK4") (pin "4") (pinfunction "C_4") (pintype "passive"))
      (node (ref "X1") (pin "3") (pinfunction "F_3") (pintype "passive"))
    )
    (net (code "72") (name "Net-(U$7-P$2)") (class "Default")
      (node (ref "R4") (pin "1") (pinfunction "1_1") (pintype "passive"))
      (node (ref "U$7") (pin "A2") (pinfunction "P$2_A2") (pintype "bidirectional"))
    )
    (net (code "73") (name "Net-(U$7-P$3)") (class "Default")
      (node (ref "R3") (pin "1") (pinfunction "1_1") (pintype "passive"))
      (node (ref "U$7") (pin "A3") (pinfunction "P$3_A3") (pintype "bidirectional"))
    )
    (net (code "74") (name "RES") (class "Default")
      (node (ref "GND") (pin "RES") (pinfunction "RES_RES") (pintype "bidirectional"))
    )
    (net (code "75") (name "VIN") (class "Default")
      (node (ref "GND") (pin "VIN") (pinfunction "VIN_VIN") (pintype "bidirectional"))
    )
    (net (code "76") (name "unconnected-(GND-*D5-PadD5)") (class "Default")
      (node (ref "GND") (pin "D5") (pinfunction "*D5_D5") (pintype "bidirectional"))
    )
    (net (code "77") (name "unconnected-(GND-*D6-PadD6)") (class "Default")
      (node (ref "GND") (pin "D6") (pinfunction "*D6_D6") (pintype "bidirectional"))
    )
    (net (code "78") (name "unconnected-(GND-*D9-PadD9)") (class "Default")
      (node (ref "GND") (pin "D9") (pinfunction "*D9_D9") (pintype "bidirectional"))
    )
    (net (code "79") (name "unconnected-(GND-*D10-PadD10)") (class "Default")
      (node (ref "GND") (pin "D10") (pinfunction "*D10_D10") (pintype "bidirectional"))
    )
    (net (code "80") (name "unconnected-(GND-*D11-PadD11)") (class "Default")
      (node (ref "GND") (pin "D11") (pinfunction "*D11_D11") (pintype "bidirectional"))
    )
    (net (code "81") (name "unconnected-(GND-Pad3.3V)") (class "Default")
      (node (ref "GND") (pin "3.3V") (pinfunction "3.3V_3.3V") (pintype "bidirectional"))
    )
    (net (code "82") (name "unconnected-(GND-PadA0)") (class "Default")
      (node (ref "GND") (pin "A0") (pinfunction "A0_A0") (pintype "bidirectional"))
    )
    (net (code "83") (name "unconnected-(GND-PadA2)") (class "Default")
      (node (ref "GND") (pin "A2") (pinfunction "A2_A2") (pintype "bidirectional"))
    )
    (net (code "84") (name "unconnected-(GND-PadA3)") (class "Default")
      (node (ref "GND") (pin "A3") (pinfunction "A3_A3") (pintype "bidirectional"))
    )
    (net (code "85") (name "unconnected-(GND-PadA4)") (class "Default")
      (node (ref "GND") (pin "A4") (pinfunction "A4_A4") (pintype "bidirectional"))
    )
    (net (code "86") (name "unconnected-(GND-PadA5)") (class "Default")
      (node (ref "GND") (pin "A5") (pinfunction "A5_A5") (pintype "bidirectional"))
    )
    (net (code "87") (name "unconnected-(GND-PadAREF)") (class "Default")
      (node (ref "GND") (pin "AREF") (pinfunction "AREF_AREF") (pintype "bidirectional"))
    )
    (net (code "88") (name "unconnected-(GND-PadD4)") (class "Default")
      (node (ref "GND") (pin "D4") (pinfunction "D4_D4") (pintype "bidirectional"))
    )
    (net (code "89") (name "unconnected-(GND-PadD7)") (class "Default")
      (node (ref "GND") (pin "D7") (pinfunction "D7_D7") (pintype "bidirectional"))
    )
    (net (code "90") (name "unconnected-(GND-PadD8)") (class "Default")
      (node (ref "GND") (pin "D8") (pinfunction "D8_D8") (pintype "bidirectional"))
    )
    (net (code "91") (name "unconnected-(GND-PadD12)") (class "Default")
      (node (ref "GND") (pin "D12") (pinfunction "D12_D12") (pintype "bidirectional"))
    )
    (net (code "92") (name "unconnected-(GND-PadD13)") (class "Default")
      (node (ref "GND") (pin "D13") (pinfunction "D13_D13") (pintype "bidirectional"))
    )
    (net (code "93") (name "unconnected-(GND-PadRX)") (class "Default")
      (node (ref "GND") (pin "RX") (pinfunction "RX_RX") (pintype "bidirectional"))
    )
    (net (code "94") (name "unconnected-(GND-PadTX)") (class "Default")
      (node (ref "GND") (pin "TX") (pinfunction "TX_TX") (pintype "bidirectional"))
    )
    (net (code "95") (name "unconnected-(IC2-INTA-Pad20)") (class "Default")
      (node (ref "IC2") (pin "20") (pinfunction "INTA_20") (pintype "output"))
    )
    (net (code "96") (name "unconnected-(IC2-INTB-Pad19)") (class "Default")
      (node (ref "IC2") (pin "19") (pinfunction "INTB_19") (pintype "output"))
    )
    (net (code "97") (name "unconnected-(JP1-Pad1)") (class "Default")
      (node (ref "JP1") (pin "1") (pinfunction "1_1") (pintype "passive"))
    )
    (net (code "98") (name "unconnected-(JP1-Pad2)") (class "Default")
      (node (ref "JP1") (pin "2") (pinfunction "2_2") (pintype "passive"))
    )
    (net (code "99") (name "unconnected-(K1B-O-PadO1)") (class "Default")
      (node (ref "K1") (pin "O1") (pinfunction "O_O1") (pintype "passive"))
    )
    (net (code "100") (name "unconnected-(K1C-O-PadO2)") (class "Default")
      (node (ref "K1") (pin "O2") (pinfunction "O_O2") (pintype "passive"))
    )
    (net (code "101") (name "unconnected-(K2B-O-PadO1)") (class "Default")
      (node (ref "K2") (pin "O1") (pinfunction "O_O1") (pintype "passive"))
    )
    (net (code "102") (name "unconnected-(K2C-O-PadO2)") (class "Default")
      (node (ref "K2") (pin "O2") (pinfunction "O_O2") (pintype "passive"))
    )
    (net (code "103") (name "unconnected-(K3B-O-PadO1)") (class "Default")
      (node (ref "K3") (pin "O1") (pinfunction "O_O1") (pintype "passive"))
    )
    (net (code "104") (name "unconnected-(K3C-O-PadO2)") (class "Default")
      (node (ref "K3") (pin "O2") (pinfunction "O_O2") (pintype "passive"))
    )
    (net (code "105") (name "unconnected-(K4B-O-PadO1)") (class "Default")
      (node (ref "K4") (pin "O1") (pinfunction "O_O1") (pintype "passive"))
    )
    (net (code "106") (name "unconnected-(K4C-O-PadO2)") (class "Default")
      (node (ref "K4") (pin "O2") (pinfunction "O_O2") (pintype "passive"))
    )
    (net (code "107") (name "unconnected-(K5B-O-PadO1)") (class "Default")
      (node (ref "K5") (pin "O1") (pinfunction "O_O1") (pintype "passive"))
    )
    (net (code "108") (name "unconnected-(K5C-O-PadO2)") (class "Default")
      (node (ref "K5") (pin "O2") (pinfunction "O_O2") (pintype "passive"))
    )
    (net (code "109") (name "unconnected-(K6B-O-PadO1)") (class "Default")
      (node (ref "K6") (pin "O1") (pinfunction "O_O1") (pintype "passive"))
    )
    (net (code "110") (name "unconnected-(K6C-O-PadO2)") (class "Default")
      (node (ref "K6") (pin "O2") (pinfunction "O_O2") (pintype "passive"))
    )
    (net (code "111") (name "unconnected-(K7B-O-PadO1)") (class "Default")
      (node (ref "K7") (pin "O1") (pinfunction "O_O1") (pintype "passive"))
    )
    (net (code "112") (name "unconnected-(K7C-O-PadO2)") (class "Default")
      (node (ref "K7") (pin "O2") (pinfunction "O_O2") (pintype "passive"))
    )
    (net (code "113") (name "unconnected-(K8B-O-PadO1)") (class "Default")
      (node (ref "K8") (pin "O1") (pinfunction "O_O1") (pintype "passive"))
    )
    (net (code "114") (name "unconnected-(K8C-O-PadO2)") (class "Default")
      (node (ref "K8") (pin "O2") (pinfunction "O_O2") (pintype "passive"))
    )
  )
)
